# Main.net
KiCad netlist of a schematic drawn in EAGLE
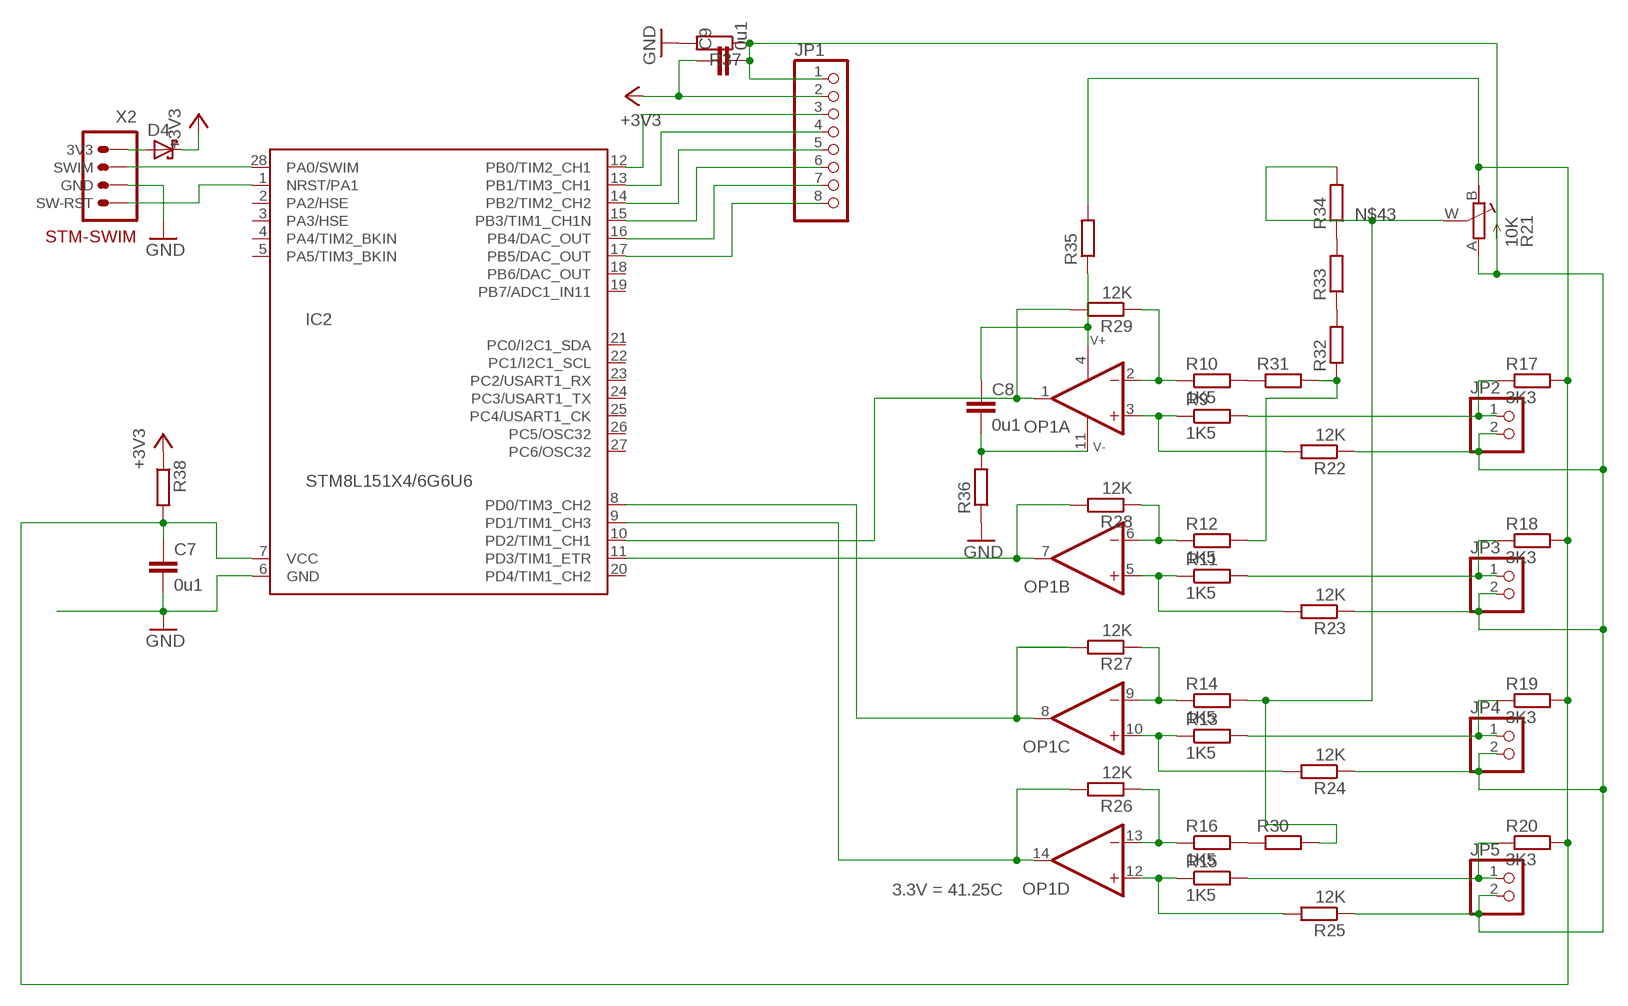
[diagram p0: schematic, sheet 1]
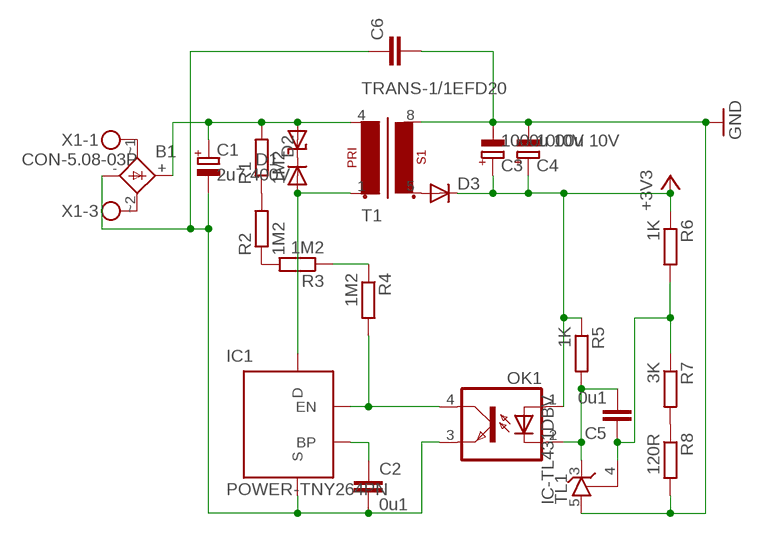
[diagram p1: schematic, sheet 2]

(export (version "E")
  (design (tool "Eeschema 10.0.6"))
  (components
    (comp (ref "B1")
      (value "RECTIFIERSOIC-8")
      (footprint "eagle-import:SOIC-4")
      (libsource (lib "eagle-import") (part "RECTIFIERSOIC-8"))
    )
    (comp (ref "C1")
      (value "2u7 400V")
      (footprint "eagle-import:E5-10,5")
      (libsource (lib "eagle-import") (part "CAP-POL_E5-10.5"))
    )
    (comp (ref "C2")
      (value "0u1")
      (footprint "eagle-import:C0805")
      (libsource (lib "eagle-import") (part "CAP_0805"))
    )
    (comp (ref "C3")
      (value "1000u 10V")
      (footprint "eagle-import:E5-10,5")
      (libsource (lib "eagle-import") (part "CAP-POL_E5-10.5"))
    )
    (comp (ref "C4")
      (value "1000u 10V")
      (footprint "eagle-import:E5-10,5")
      (libsource (lib "eagle-import") (part "CAP-POL_E5-10.5"))
    )
    (comp (ref "C5")
      (value "0u1")
      (footprint "eagle-import:C0805")
      (libsource (lib "eagle-import") (part "CAP_0805"))
    )
    (comp (ref "C6")
      (value "CAP_C50-024X044")
      (footprint "eagle-import:C050-024X044")
      (libsource (lib "eagle-import") (part "CAP_C50-024X044"))
    )
    (comp (ref "D1")
      (value "SUPRESSORDO-204AC")
      (footprint "eagle-import:DO15-12")
      (libsource (lib "eagle-import") (part "SUPRESSORDO-204AC"))
    )
    (comp (ref "D2")
      (value "DIODE_ES1J")
      (footprint "eagle-import:DO214AC")
      (libsource (lib "eagle-import") (part "DIODE_ES1J"))
    )
    (comp (ref "D3")
      (value "DIODE_ES1J")
      (footprint "eagle-import:DO214AC")
      (libsource (lib "eagle-import") (part "DIODE_ES1J"))
    )
    (comp (ref "IC1")
      (value "POWER-TNY264PN")
      (footprint "eagle-import:DIP-8B")
      (libsource (lib "eagle-import") (part "POWER-TNY264PN"))
    )
    (comp (ref "OK1")
      (value "OPTOTRANSPC817")
      (footprint "eagle-import:DIL04")
      (fields (field (name "MPN") "PC817X4J000F"))
      (libsource (lib "eagle-import") (part "OPTOTRANSPC817"))
    )
    (comp (ref "R1")
      (value "1M2")
      (footprint "eagle-import:R0805")
      (libsource (lib "eagle-import") (part "R_0805"))
    )
    (comp (ref "R2")
      (value "1M2")
      (footprint "eagle-import:R0805")
      (libsource (lib "eagle-import") (part "R_0805"))
    )
    (comp (ref "R3")
      (value "1M2")
      (footprint "eagle-import:R0805")
      (libsource (lib "eagle-import") (part "R_0805"))
    )
    (comp (ref "R4")
      (value "1M2")
      (footprint "eagle-import:R0805")
      (libsource (lib "eagle-import") (part "R_0805"))
    )
    (comp (ref "R5")
      (value "1K")
      (footprint "eagle-import:R0805")
      (libsource (lib "eagle-import") (part "R_0805"))
    )
    (comp (ref "R6")
      (value "1K")
      (footprint "eagle-import:R0805")
      (libsource (lib "eagle-import") (part "R_0805"))
    )
    (comp (ref "R7")
      (value "3K")
      (footprint "eagle-import:R0805")
      (libsource (lib "eagle-import") (part "R_0805"))
    )
    (comp (ref "R8")
      (value "120R")
      (footprint "eagle-import:R0805")
      (libsource (lib "eagle-import") (part "R_0805"))
    )
    (comp (ref "T1")
      (value "TRANS-1/1EFD20")
      (footprint "eagle-import:EFD20_8PIN")
      (libsource (lib "eagle-import") (part "TRANS-1/1EFD20"))
    )
    (comp (ref "TL1")
      (value "IC-TL431DBV")
      (footprint "eagle-import:SOT23-5L")
      (libsource (lib "eagle-import") (part "IC-TL431DBV"))
    )
    (comp (ref "X1")
      (value "CON-5.08-03P")
      (footprint "eagle-import:MKDSN1,5_3-5,08")
      (libsource (lib "eagle-import") (part "CON-5.08-03P"))
    )
    (comp (ref "C7")
      (value "0u1")
      (footprint "eagle-import:C0805")
      (libsource (lib "eagle-import") (part "CAP_0805"))
    )
    (comp (ref "C8")
      (value "0u1")
      (footprint "eagle-import:C0805")
      (libsource (lib "eagle-import") (part "CAP_0805"))
    )
    (comp (ref "C9")
      (value "0u1")
      (footprint "eagle-import:C0805")
      (libsource (lib "eagle-import") (part "CAP_0805"))
    )
    (comp (ref "D4")
      (value "DIODE-SH_SOD523")
      (footprint "eagle-import:SOD523")
      (libsource (lib "eagle-import") (part "DIODE-SH_SOD523"))
    )
    (comp (ref "IC2")
      (value "STM8L151X4/6G6U6")
      (footprint "eagle-import:QFN28")
      (libsource (lib "eagle-import") (part "STM8L151X4/6G6U6"))
    )
    (comp (ref "JP1")
      (value "PINHD-1X8")
      (footprint "eagle-import:1X08")
      (libsource (lib "eagle-import") (part "PINHD-1X8"))
    )
    (comp (ref "JP2")
      (value "PINHD-1X2")
      (footprint "eagle-import:1X02")
      (libsource (lib "eagle-import") (part "PINHD-1X2"))
    )
    (comp (ref "JP3")
      (value "PINHD-1X2")
      (footprint "eagle-import:1X02")
      (libsource (lib "eagle-import") (part "PINHD-1X2"))
    )
    (comp (ref "JP4")
      (value "PINHD-1X2")
      (footprint "eagle-import:1X02")
      (libsource (lib "eagle-import") (part "PINHD-1X2"))
    )
    (comp (ref "JP5")
      (value "PINHD-1X2")
      (footprint "eagle-import:1X02")
      (libsource (lib "eagle-import") (part "PINHD-1X2"))
    )
    (comp (ref "OP1")
      (value "OP-AMP-4LMV324IPT")
      (footprint "eagle-import:TSSOP14")
      (libsource (lib "eagle-import") (part "OP-AMP-4LMV324IPT"))
    )
    (comp (ref "R9")
      (value "1K5")
      (footprint "eagle-import:R0805")
      (libsource (lib "eagle-import") (part "R_0805"))
    )
    (comp (ref "R10")
      (value "1K5")
      (footprint "eagle-import:R0805")
      (libsource (lib "eagle-import") (part "R_0805"))
    )
    (comp (ref "R11")
      (value "1K5")
      (footprint "eagle-import:R0805")
      (libsource (lib "eagle-import") (part "R_0805"))
    )
    (comp (ref "R12")
      (value "1K5")
      (footprint "eagle-import:R0805")
      (libsource (lib "eagle-import") (part "R_0805"))
    )
    (comp (ref "R13")
      (value "1K5")
      (footprint "eagle-import:R0805")
      (libsource (lib "eagle-import") (part "R_0805"))
    )
    (comp (ref "R14")
      (value "1K5")
      (footprint "eagle-import:R0805")
      (libsource (lib "eagle-import") (part "R_0805"))
    )
    (comp (ref "R15")
      (value "1K5")
      (footprint "eagle-import:R0805")
      (libsource (lib "eagle-import") (part "R_0805"))
    )
    (comp (ref "R16")
      (value "1K5")
      (footprint "eagle-import:R0805")
      (libsource (lib "eagle-import") (part "R_0805"))
    )
    (comp (ref "R17")
      (value "3K3")
      (footprint "eagle-import:R0805")
      (libsource (lib "eagle-import") (part "R_0805"))
    )
    (comp (ref "R18")
      (value "3K3")
      (footprint "eagle-import:R0805")
      (libsource (lib "eagle-import") (part "R_0805"))
    )
    (comp (ref "R19")
      (value "3K3")
      (footprint "eagle-import:R0805")
      (libsource (lib "eagle-import") (part "R_0805"))
    )
    (comp (ref "R20")
      (value "3K3")
      (footprint "eagle-import:R0805")
      (libsource (lib "eagle-import") (part "R_0805"))
    )
    (comp (ref "R21")
      (value "10K")
      (footprint "eagle-import:RJ9W")
      (libsource (lib "eagle-import") (part "R_POTTURN-X"))
    )
    (comp (ref "R22")
      (value "12K")
      (footprint "eagle-import:R0805")
      (libsource (lib "eagle-import") (part "R_0805"))
    )
    (comp (ref "R23")
      (value "12K")
      (footprint "eagle-import:R0805")
      (libsource (lib "eagle-import") (part "R_0805"))
    )
    (comp (ref "R24")
      (value "12K")
      (footprint "eagle-import:R0805")
      (libsource (lib "eagle-import") (part "R_0805"))
    )
    (comp (ref "R25")
      (value "12K")
      (footprint "eagle-import:R0805")
      (libsource (lib "eagle-import") (part "R_0805"))
    )
    (comp (ref "R26")
      (value "12K")
      (footprint "eagle-import:R0805")
      (libsource (lib "eagle-import") (part "R_0805"))
    )
    (comp (ref "R27")
      (value "12K")
      (footprint "eagle-import:R0805")
      (libsource (lib "eagle-import") (part "R_0805"))
    )
    (comp (ref "R28")
      (value "12K")
      (footprint "eagle-import:R0805")
      (libsource (lib "eagle-import") (part "R_0805"))
    )
    (comp (ref "R29")
      (value "12K")
      (footprint "eagle-import:R0805")
      (libsource (lib "eagle-import") (part "R_0805"))
    )
    (comp (ref "R30")
      (value "R_1206")
      (footprint "eagle-import:R1206")
      (libsource (lib "eagle-import") (part "R_1206"))
    )
    (comp (ref "R31")
      (value "R_1206")
      (footprint "eagle-import:R1206")
      (libsource (lib "eagle-import") (part "R_1206"))
    )
    (comp (ref "R32")
      (value "R_1206")
      (footprint "eagle-import:R1206")
      (libsource (lib "eagle-import") (part "R_1206"))
    )
    (comp (ref "R33")
      (value "R_1206")
      (footprint "eagle-import:R1206")
      (libsource (lib "eagle-import") (part "R_1206"))
    )
    (comp (ref "R34")
      (value "R_1206")
      (footprint "eagle-import:R1206")
      (libsource (lib "eagle-import") (part "R_1206"))
    )
    (comp (ref "R35")
      (value "R_1206")
      (footprint "eagle-import:R1206")
      (libsource (lib "eagle-import") (part "R_1206"))
    )
    (comp (ref "R36")
      (value "R_1206")
      (footprint "eagle-import:R1206")
      (libsource (lib "eagle-import") (part "R_1206"))
    )
    (comp (ref "R37")
      (value "R_1206")
      (footprint "eagle-import:R1206")
      (libsource (lib "eagle-import") (part "R_1206"))
    )
    (comp (ref "R38")
      (value "R_1206")
      (footprint "eagle-import:R1206")
      (libsource (lib "eagle-import") (part "R_1206"))
    )
    (comp (ref "X2")
      (value "STM-SWIMPINS")
      (footprint "eagle-import:1X04_90")
      (libsource (lib "eagle-import") (part "STM-SWIMPINS"))
    )
  )
  (nets
    (net (code "1") (name "+3V3") (class "Default")
      (node (ref "C3") (pin "+") (pinfunction "+_+") (pintype "passive"))
      (node (ref "C4") (pin "+") (pinfunction "+_+") (pintype "passive"))
      (node (ref "C9") (pin "1") (pinfunction "1_1") (pintype "passive"))
      (node (ref "D3") (pin "C") (pinfunction "C_C") (pintype "passive"))
      (node (ref "D4") (pin "C") (pinfunction "C_C") (pintype "passive"))
      (node (ref "JP1") (pin "2") (pinfunction "2_2") (pintype "passive"))
      (node (ref "OK1") (pin "1") (pinfunction "A_1") (pintype "passive"))
      (node (ref "R38") (pin "1") (pinfunction "1_1") (pintype "passive"))
      (node (ref "R5") (pin "1") (pinfunction "1_1") (pintype "passive"))
      (node (ref "R6") (pin "1") (pinfunction "1_1") (pintype "passive"))
    )
    (net (code "2") (name "GND") (class "Default")
      (node (ref "C3") (pin "-") (pinfunction "-_-") (pintype "passive"))
      (node (ref "C4") (pin "-") (pinfunction "-_-") (pintype "passive"))
      (node (ref "C6") (pin "2") (pinfunction "2_2") (pintype "passive"))
      (node (ref "C7") (pin "2") (pinfunction "2_2") (pintype "passive"))
      (node (ref "IC2") (pin "6") (pinfunction "GND_6") (pintype "power_in"))
      (node (ref "R36") (pin "1") (pinfunction "1_1") (pintype "passive"))
      (node (ref "R37") (pin "2") (pinfunction "2_2") (pintype "passive"))
      (node (ref "R8") (pin "2") (pinfunction "2_2") (pintype "passive"))
      (node (ref "T1") (pin "8") (pinfunction "S1-2_8") (pintype "passive"))
      (node (ref "TL1") (pin "5") (pinfunction "A_5") (pintype "passive"))
      (node (ref "X2") (pin "3") (pinfunction "GND_3") (pintype "passive"))
    )
    (net (code "3") (name "N$43") (class "Default")
      (node (ref "R14") (pin "2") (pinfunction "2_2") (pintype "passive"))
      (node (ref "R21") (pin "W") (pinfunction "S_W") (pintype "passive"))
      (node (ref "R30") (pin "2") (pinfunction "2_2") (pintype "passive"))
      (node (ref "R34") (pin "2") (pinfunction "2_2") (pintype "passive"))
    )
    (net (code "4") (name "Net-(B1-AC1)") (class "Default")
      (node (ref "B1") (pin "~1") (pinfunction "AC1_~1") (pintype "passive"))
      (node (ref "X1") (pin "1") (pinfunction "KL_1") (pintype "passive"))
    )
    (net (code "5") (name "Net-(B1-AC2)") (class "Default")
      (node (ref "B1") (pin "~2") (pinfunction "AC2_~2") (pintype "passive"))
      (node (ref "X1") (pin "3") (pinfunction "KL_3") (pintype "passive"))
    )
    (net (code "6") (name "Net-(C9-Pad2)") (class "Default")
      (node (ref "C9") (pin "2") (pinfunction "2_2") (pintype "passive"))
      (node (ref "JP1") (pin "1") (pinfunction "1_1") (pintype "passive"))
      (node (ref "JP2") (pin "2") (pinfunction "2_2") (pintype "passive"))
      (node (ref "JP3") (pin "2") (pinfunction "2_2") (pintype "passive"))
      (node (ref "JP4") (pin "2") (pinfunction "2_2") (pintype "passive"))
      (node (ref "JP5") (pin "2") (pinfunction "2_2") (pintype "passive"))
      (node (ref "R21") (pin "A") (pinfunction "A_A") (pintype "passive"))
      (node (ref "R22") (pin "1") (pinfunction "1_1") (pintype "passive"))
      (node (ref "R23") (pin "1") (pinfunction "1_1") (pintype "passive"))
      (node (ref "R24") (pin "1") (pinfunction "1_1") (pintype "passive"))
      (node (ref "R25") (pin "1") (pinfunction "1_1") (pintype "passive"))
      (node (ref "R37") (pin "1") (pinfunction "1_1") (pintype "passive"))
    )
    (net (code "7") (name "Net-(D1-PadC)") (class "Default")
      (node (ref "D1") (pin "C") (pinfunction "C_C") (pintype "passive"))
      (node (ref "D2") (pin "C") (pinfunction "C_C") (pintype "passive"))
    )
    (net (code "8") (name "Net-(IC1-BP)") (class "Default")
      (node (ref "C2") (pin "1") (pinfunction "1_1") (pintype "passive"))
      (node (ref "IC1") (pin "1") (pinfunction "BP_1") (pintype "input"))
    )
    (net (code "9") (name "Net-(IC1-D)") (class "Default")
      (node (ref "D2") (pin "A") (pinfunction "A_A") (pintype "passive"))
      (node (ref "IC1") (pin "5") (pinfunction "D_5") (pintype "input"))
      (node (ref "T1") (pin "1") (pinfunction "P1-1_1") (pintype "passive"))
    )
    (net (code "10") (name "Net-(IC1-EN)") (class "Default")
      (node (ref "IC1") (pin "4") (pinfunction "EN_4") (pintype "input"))
      (node (ref "OK1") (pin "4") (pinfunction "COL_4") (pintype "passive"))
      (node (ref "R4") (pin "2") (pinfunction "2_2") (pintype "passive"))
    )
    (net (code "11") (name "Net-(IC2-NRST{slash}PA1)") (class "Default")
      (node (ref "IC2") (pin "1") (pinfunction "NRST/PA1_1") (pintype "bidirectional"))
      (node (ref "X2") (pin "4") (pinfunction "SW-RST_4") (pintype "passive"))
    )
    (net (code "12") (name "Net-(IC2-PA0{slash}SWIM)") (class "Default")
      (node (ref "IC2") (pin "28") (pinfunction "PA0/SWIM_28") (pintype "bidirectional"))
      (node (ref "X2") (pin "2") (pinfunction "SWIM_2") (pintype "passive"))
    )
    (net (code "13") (name "Net-(IC2-PB0{slash}TIM2_CH1)") (class "Default")
      (node (ref "IC2") (pin "12") (pinfunction "PB0/TIM2_CH1_12") (pintype "bidirectional"))
      (node (ref "JP1") (pin "3") (pinfunction "3_3") (pintype "passive"))
    )
    (net (code "14") (name "Net-(IC2-PB1{slash}TIM3_CH1)") (class "Default")
      (node (ref "IC2") (pin "13") (pinfunction "PB1/TIM3_CH1_13") (pintype "bidirectional"))
      (node (ref "JP1") (pin "4") (pinfunction "4_4") (pintype "passive"))
    )
    (net (code "15") (name "Net-(IC2-PB2{slash}TIM2_CH2)") (class "Default")
      (node (ref "IC2") (pin "14") (pinfunction "PB2/TIM2_CH2_14") (pintype "bidirectional"))
      (node (ref "JP1") (pin "5") (pinfunction "5_5") (pintype "passive"))
    )
    (net (code "16") (name "Net-(IC2-PB3{slash}TIM1_CH1N)") (class "Default")
      (node (ref "IC2") (pin "15") (pinfunction "PB3/TIM1_CH1N_15") (pintype "bidirectional"))
      (node (ref "JP1") (pin "6") (pinfunction "6_6") (pintype "passive"))
    )
    (net (code "17") (name "Net-(IC2-PB4{slash}DAC_OUT)") (class "Default")
      (node (ref "IC2") (pin "16") (pinfunction "PB4/DAC_OUT_16") (pintype "bidirectional"))
      (node (ref "JP1") (pin "7") (pinfunction "7_7") (pintype "passive"))
    )
    (net (code "18") (name "Net-(IC2-PB5{slash}DAC_OUT)") (class "Default")
      (node (ref "IC2") (pin "17") (pinfunction "PB5/DAC_OUT_17") (pintype "bidirectional"))
      (node (ref "JP1") (pin "8") (pinfunction "8_8") (pintype "passive"))
    )
    (net (code "19") (name "Net-(IC2-PD0{slash}TIM3_CH2)") (class "Default")
      (node (ref "IC2") (pin "8") (pinfunction "PD0/TIM3_CH2_8") (pintype "bidirectional"))
      (node (ref "OP1") (pin "8") (pinfunction "OUT_8") (pintype "output"))
      (node (ref "R27") (pin "2") (pinfunction "2_2") (pintype "passive"))
    )
    (net (code "20") (name "Net-(IC2-PD1{slash}TIM1_CH3)") (class "Default")
      (node (ref "IC2") (pin "9") (pinfunction "PD1/TIM1_CH3_9") (pintype "bidirectional"))
      (node (ref "OP1") (pin "14") (pinfunction "OUT_14") (pintype "output"))
      (node (ref "R26") (pin "2") (pinfunction "2_2") (pintype "passive"))
    )
    (net (code "21") (name "Net-(IC2-PD2{slash}TIM1_CH1)") (class "Default")
      (node (ref "IC2") (pin "10") (pinfunction "PD2/TIM1_CH1_10") (pintype "bidirectional"))
      (node (ref "OP1") (pin "1") (pinfunction "OUT_1") (pintype "output"))
      (node (ref "R29") (pin "2") (pinfunction "2_2") (pintype "passive"))
    )
    (net (code "22") (name "Net-(IC2-PD3{slash}TIM1_ETR)") (class "Default")
      (node (ref "IC2") (pin "11") (pinfunction "PD3/TIM1_ETR_11") (pintype "bidirectional"))
      (node (ref "OP1") (pin "7") (pinfunction "OUT_7") (pintype "output"))
      (node (ref "R28") (pin "2") (pinfunction "2_2") (pintype "passive"))
    )
    (net (code "23") (name "Net-(IC2-VCC)") (class "Default")
      (node (ref "C7") (pin "1") (pinfunction "1_1") (pintype "passive"))
      (node (ref "IC2") (pin "7") (pinfunction "VCC_7") (pintype "power_in"))
      (node (ref "R17") (pin "2") (pinfunction "2_2") (pintype "passive"))
      (node (ref "R18") (pin "2") (pinfunction "2_2") (pintype "passive"))
      (node (ref "R19") (pin "2") (pinfunction "2_2") (pintype "passive"))
      (node (ref "R20") (pin "2") (pinfunction "2_2") (pintype "passive"))
      (node (ref "R21") (pin "B") (pinfunction "E_B") (pintype "passive"))
      (node (ref "R35") (pin "2") (pinfunction "2_2") (pintype "passive"))
      (node (ref "R38") (pin "2") (pinfunction "2_2") (pintype "passive"))
    )
    (net (code "24") (name "Net-(JP2-Pad1)") (class "Default")
      (node (ref "JP2") (pin "1") (pinfunction "1_1") (pintype "passive"))
      (node (ref "R17") (pin "1") (pinfunction "1_1") (pintype "passive"))
      (node (ref "R9") (pin "2") (pinfunction "2_2") (pintype "passive"))
    )
    (net (code "25") (name "Net-(JP3-Pad1)") (class "Default")
      (node (ref "JP3") (pin "1") (pinfunction "1_1") (pintype "passive"))
      (node (ref "R11") (pin "2") (pinfunction "2_2") (pintype "passive"))
      (node (ref "R18") (pin "1") (pinfunction "1_1") (pintype "passive"))
    )
    (net (code "26") (name "Net-(JP4-Pad1)") (class "Default")
      (node (ref "JP4") (pin "1") (pinfunction "1_1") (pintype "passive"))
      (node (ref "R13") (pin "2") (pinfunction "2_2") (pintype "passive"))
      (node (ref "R19") (pin "1") (pinfunction "1_1") (pintype "passive"))
    )
    (net (code "27") (name "Net-(JP5-Pad1)") (class "Default")
      (node (ref "JP5") (pin "1") (pinfunction "1_1") (pintype "passive"))
      (node (ref "R15") (pin "2") (pinfunction "2_2") (pintype "passive"))
      (node (ref "R20") (pin "1") (pinfunction "1_1") (pintype "passive"))
    )
    (net (code "28") (name "Net-(OK1-C)") (class "Default")
      (node (ref "C5") (pin "2") (pinfunction "2_2") (pintype "passive"))
      (node (ref "OK1") (pin "2") (pinfunction "C_2") (pintype "passive"))
      (node (ref "R5") (pin "2") (pinfunction "2_2") (pintype "passive"))
      (node (ref "TL1") (pin "3") (pinfunction "C_3") (pintype "passive"))
    )
    (net (code "29") (name "Net-(OK1-EMIT)") (class "Default")
      (node (ref "B1") (pin "-") (pinfunction "-_-") (pintype "passive"))
      (node (ref "C1") (pin "-") (pinfunction "-_-") (pintype "passive"))
      (node (ref "C2") (pin "2") (pinfunction "2_2") (pintype "passive"))
      (node (ref "C6") (pin "1") (pinfunction "1_1") (pintype "passive"))
      (node (ref "IC1") (pin "2") (pinfunction "S_2") (pintype "input"))
      (node (ref "IC1") (pin "3") (pinfunction "S_3") (pintype "input"))
      (node (ref "IC1") (pin "7") (pinfunction "S_7") (pintype "input"))
      (node (ref "IC1") (pin "8") (pinfunction "S_8") (pintype "input"))
      (node (ref "OK1") (pin "3") (pinfunction "EMIT_3") (pintype "passive"))
    )
    (net (code "30") (name "Net-(OP1A-+IN)") (class "Default")
      (node (ref "OP1") (pin "3") (pinfunction "+IN_3") (pintype "input"))
      (node (ref "R22") (pin "2") (pinfunction "2_2") (pintype "passive"))
      (node (ref "R9") (pin "1") (pinfunction "1_1") (pintype "passive"))
    )
    (net (code "31") (name "Net-(OP1A--IN)") (class "Default")
      (node (ref "OP1") (pin "2") (pinfunction "-IN_2") (pintype "input"))
      (node (ref "R10") (pin "1") (pinfunction "1_1") (pintype "passive"))
      (node (ref "R29") (pin "1") (pinfunction "1_1") (pintype "passive"))
    )
    (net (code "32") (name "Net-(OP1B-+IN)") (class "Default")
      (node (ref "OP1") (pin "5") (pinfunction "+IN_5") (pintype "input"))
      (node (ref "R11") (pin "1") (pinfunction "1_1") (pintype "passive"))
      (node (ref "R23") (pin "2") (pinfunction "2_2") (pintype "passive"))
    )
    (net (code "33") (name "Net-(OP1B--IN)") (class "Default")
      (node (ref "OP1") (pin "6") (pinfunction "-IN_6") (pintype "input"))
      (node (ref "R12") (pin "1") (pinfunction "1_1") (pintype "passive"))
      (node (ref "R28") (pin "1") (pinfunction "1_1") (pintype "passive"))
    )
    (net (code "34") (name "Net-(OP1C-+IN)") (class "Default")
      (node (ref "OP1") (pin "10") (pinfunction "+IN_10") (pintype "input"))
      (node (ref "R13") (pin "1") (pinfunction "1_1") (pintype "passive"))
      (node (ref "R24") (pin "2") (pinfunction "2_2") (pintype "passive"))
    )
    (net (code "35") (name "Net-(OP1C--IN)") (class "Default")
      (node (ref "OP1") (pin "9") (pinfunction "-IN_9") (pintype "input"))
      (node (ref "R14") (pin "1") (pinfunction "1_1") (pintype "passive"))
      (node (ref "R27") (pin "1") (pinfunction "1_1") (pintype "passive"))
    )
    (net (code "36") (name "Net-(OP1D-+IN)") (class "Default")
      (node (ref "OP1") (pin "12") (pinfunction "+IN_12") (pintype "input"))
      (node (ref "R15") (pin "1") (pinfunction "1_1") (pintype "passive"))
      (node (ref "R25") (pin "2") (pinfunction "2_2") (pintype "passive"))
    )
    (net (code "37") (name "Net-(OP1D--IN)") (class "Default")
      (node (ref "OP1") (pin "13") (pinfunction "-IN_13") (pintype "input"))
      (node (ref "R16") (pin "1") (pinfunction "1_1") (pintype "passive"))
      (node (ref "R26") (pin "1") (pinfunction "1_1") (pintype "passive"))
    )
    (net (code "38") (name "Net-(OP1E-V+)") (class "Default")
      (node (ref "C8") (pin "1") (pinfunction "1_1") (pintype "passive"))
      (node (ref "OP1") (pin "4") (pinfunction "V+_4") (pintype "power_in"))
      (node (ref "R35") (pin "1") (pinfunction "1_1") (pintype "passive"))
    )
    (net (code "39") (name "Net-(OP1E-V-)") (class "Default")
      (node (ref "C8") (pin "2") (pinfunction "2_2") (pintype "passive"))
      (node (ref "OP1") (pin "11") (pinfunction "V-_11") (pintype "power_in"))
      (node (ref "R36") (pin "2") (pinfunction "2_2") (pintype "passive"))
    )
    (net (code "40") (name "Net-(R1-Pad1)") (class "Default")
      (node (ref "R1") (pin "1") (pinfunction "1_1") (pintype "passive"))
      (node (ref "R2") (pin "2") (pinfunction "2_2") (pintype "passive"))
    )
    (net (code "41") (name "Net-(R2-Pad1)") (class "Default")
      (node (ref "R2") (pin "1") (pinfunction "1_1") (pintype "passive"))
      (node (ref "R3") (pin "2") (pinfunction "2_2") (pintype "passive"))
    )
    (net (code "42") (name "Net-(R3-Pad1)") (class "Default")
      (node (ref "R3") (pin "1") (pinfunction "1_1") (pintype "passive"))
      (node (ref "R4") (pin "1") (pinfunction "1_1") (pintype "passive"))
    )
    (net (code "43") (name "Net-(R7-Pad2)") (class "Default")
      (node (ref "R7") (pin "2") (pinfunction "2_2") (pintype "passive"))
      (node (ref "R8") (pin "1") (pinfunction "1_1") (pintype "passive"))
    )
    (net (code "44") (name "Net-(R10-Pad2)") (class "Default")
      (node (ref "R10") (pin "2") (pinfunction "2_2") (pintype "passive"))
      (node (ref "R31") (pin "1") (pinfunction "1_1") (pintype "passive"))
    )
    (net (code "45") (name "Net-(R12-Pad2)") (class "Default")
      (node (ref "R12") (pin "2") (pinfunction "2_2") (pintype "passive"))
      (node (ref "R31") (pin "2") (pinfunction "2_2") (pintype "passive"))
      (node (ref "R32") (pin "1") (pinfunction "1_1") (pintype "passive"))
    )
    (net (code "46") (name "Net-(R16-Pad2)") (class "Default")
      (node (ref "R16") (pin "2") (pinfunction "2_2") (pintype "passive"))
      (node (ref "R30") (pin "1") (pinfunction "1_1") (pintype "passive"))
    )
    (net (code "47") (name "Net-(R32-Pad2)") (class "Default")
      (node (ref "R32") (pin "2") (pinfunction "2_2") (pintype "passive"))
      (node (ref "R33") (pin "1") (pinfunction "1_1") (pintype "passive"))
    )
    (net (code "48") (name "Net-(R33-Pad2)") (class "Default")
      (node (ref "R33") (pin "2") (pinfunction "2_2") (pintype "passive"))
      (node (ref "R34") (pin "1") (pinfunction "1_1") (pintype "passive"))
    )
    (net (code "49") (name "Net-(T1-P1-2)") (class "Default")
      (node (ref "B1") (pin "+") (pinfunction "+_+") (pintype "passive"))
      (node (ref "C1") (pin "+") (pinfunction "+_+") (pintype "passive"))
      (node (ref "D1") (pin "A") (pinfunction "A_A") (pintype "passive"))
      (node (ref "R1") (pin "2") (pinfunction "2_2") (pintype "passive"))
      (node (ref "T1") (pin "4") (pinfunction "P1-2_4") (pintype "passive"))
    )
    (net (code "50") (name "Net-(T1-S1-1)") (class "Default")
      (node (ref "D3") (pin "A") (pinfunction "A_A") (pintype "passive"))
      (node (ref "T1") (pin "5") (pinfunction "S1-1_5") (pintype "passive"))
    )
    (net (code "51") (name "Net-(TL1-R)") (class "Default")
      (node (ref "C5") (pin "1") (pinfunction "1_1") (pintype "passive"))
      (node (ref "R6") (pin "2") (pinfunction "2_2") (pintype "passive"))
      (node (ref "R7") (pin "1") (pinfunction "1_1") (pintype "passive"))
      (node (ref "TL1") (pin "4") (pinfunction "R_4") (pintype "passive"))
    )
    (net (code "52") (name "Net-(X2-3V3)") (class "Default")
      (node (ref "D4") (pin "A") (pinfunction "A_A") (pintype "passive"))
      (node (ref "X2") (pin "1") (pinfunction "3V3_1") (pintype "passive"))
    )
    (net (code "53") (name "unconnected-(IC2-PA2{slash}HSE-Pad2)") (class "Default")
      (node (ref "IC2") (pin "2") (pinfunction "PA2/HSE_2") (pintype "bidirectional"))
    )
    (net (code "54") (name "unconnected-(IC2-PA3{slash}HSE-Pad3)") (class "Default")
      (node (ref "IC2") (pin "3") (pinfunction "PA3/HSE_3") (pintype "bidirectional"))
    )
    (net (code "55") (name "unconnected-(IC2-PA4{slash}TIM2_BKIN-Pad4)") (class "Default")
      (node (ref "IC2") (pin "4") (pinfunction "PA4/TIM2_BKIN_4") (pintype "bidirectional"))
    )
    (net (code "56") (name "unconnected-(IC2-PA5{slash}TIM3_BKIN-Pad5)") (class "Default")
      (node (ref "IC2") (pin "5") (pinfunction "PA5/TIM3_BKIN_5") (pintype "bidirectional"))
    )
    (net (code "57") (name "unconnected-(IC2-PB6{slash}DAC_OUT-Pad18)") (class "Default")
      (node (ref "IC2") (pin "18") (pinfunction "PB6/DAC_OUT_18") (pintype "bidirectional"))
    )
    (net (code "58") (name "unconnected-(IC2-PB7{slash}ADC1_IN11-Pad19)") (class "Default")
      (node (ref "IC2") (pin "19") (pinfunction "PB7/ADC1_IN11_19") (pintype "bidirectional"))
    )
    (net (code "59") (name "unconnected-(IC2-PC0{slash}I2C1_SDA-Pad21)") (class "Default")
      (node (ref "IC2") (pin "21") (pinfunction "PC0/I2C1_SDA_21") (pintype "bidirectional"))
    )
    (net (code "60") (name "unconnected-(IC2-PC1{slash}I2C1_SCL-Pad22)") (class "Default")
      (node (ref "IC2") (pin "22") (pinfunction "PC1/I2C1_SCL_22") (pintype "bidirectional"))
    )
    (net (code "61") (name "unconnected-(IC2-PC2{slash}USART1_RX-Pad23)") (class "Default")
      (node (ref "IC2") (pin "23") (pinfunction "PC2/USART1_RX_23") (pintype "bidirectional"))
    )
    (net (code "62") (name "unconnected-(IC2-PC3{slash}USART1_TX-Pad24)") (class "Default")
      (node (ref "IC2") (pin "24") (pinfunction "PC3/USART1_TX_24") (pintype "bidirectional"))
    )
    (net (code "63") (name "unconnected-(IC2-PC4{slash}USART1_CK-Pad25)") (class "Default")
      (node (ref "IC2") (pin "25") (pinfunction "PC4/USART1_CK_25") (pintype "bidirectional"))
    )
    (net (code "64") (name "unconnected-(IC2-PC5{slash}OSC32-Pad26)") (class "Default")
      (node (ref "IC2") (pin "26") (pinfunction "PC5/OSC32_26") (pintype "bidirectional"))
    )
    (net (code "65") (name "unconnected-(IC2-PC6{slash}OSC32-Pad27)") (class "Default")
      (node (ref "IC2") (pin "27") (pinfunction "PC6/OSC32_27") (pintype "bidirectional"))
    )
    (net (code "66") (name "unconnected-(IC2-PD4{slash}TIM1_CH2-Pad20)") (class "Default")
      (node (ref "IC2") (pin "20") (pinfunction "PD4/TIM1_CH2_20") (pintype "bidirectional"))
    )
  )
)
